# Electronical_dice.net
KiCad netlist of a schematic drawn in EAGLE
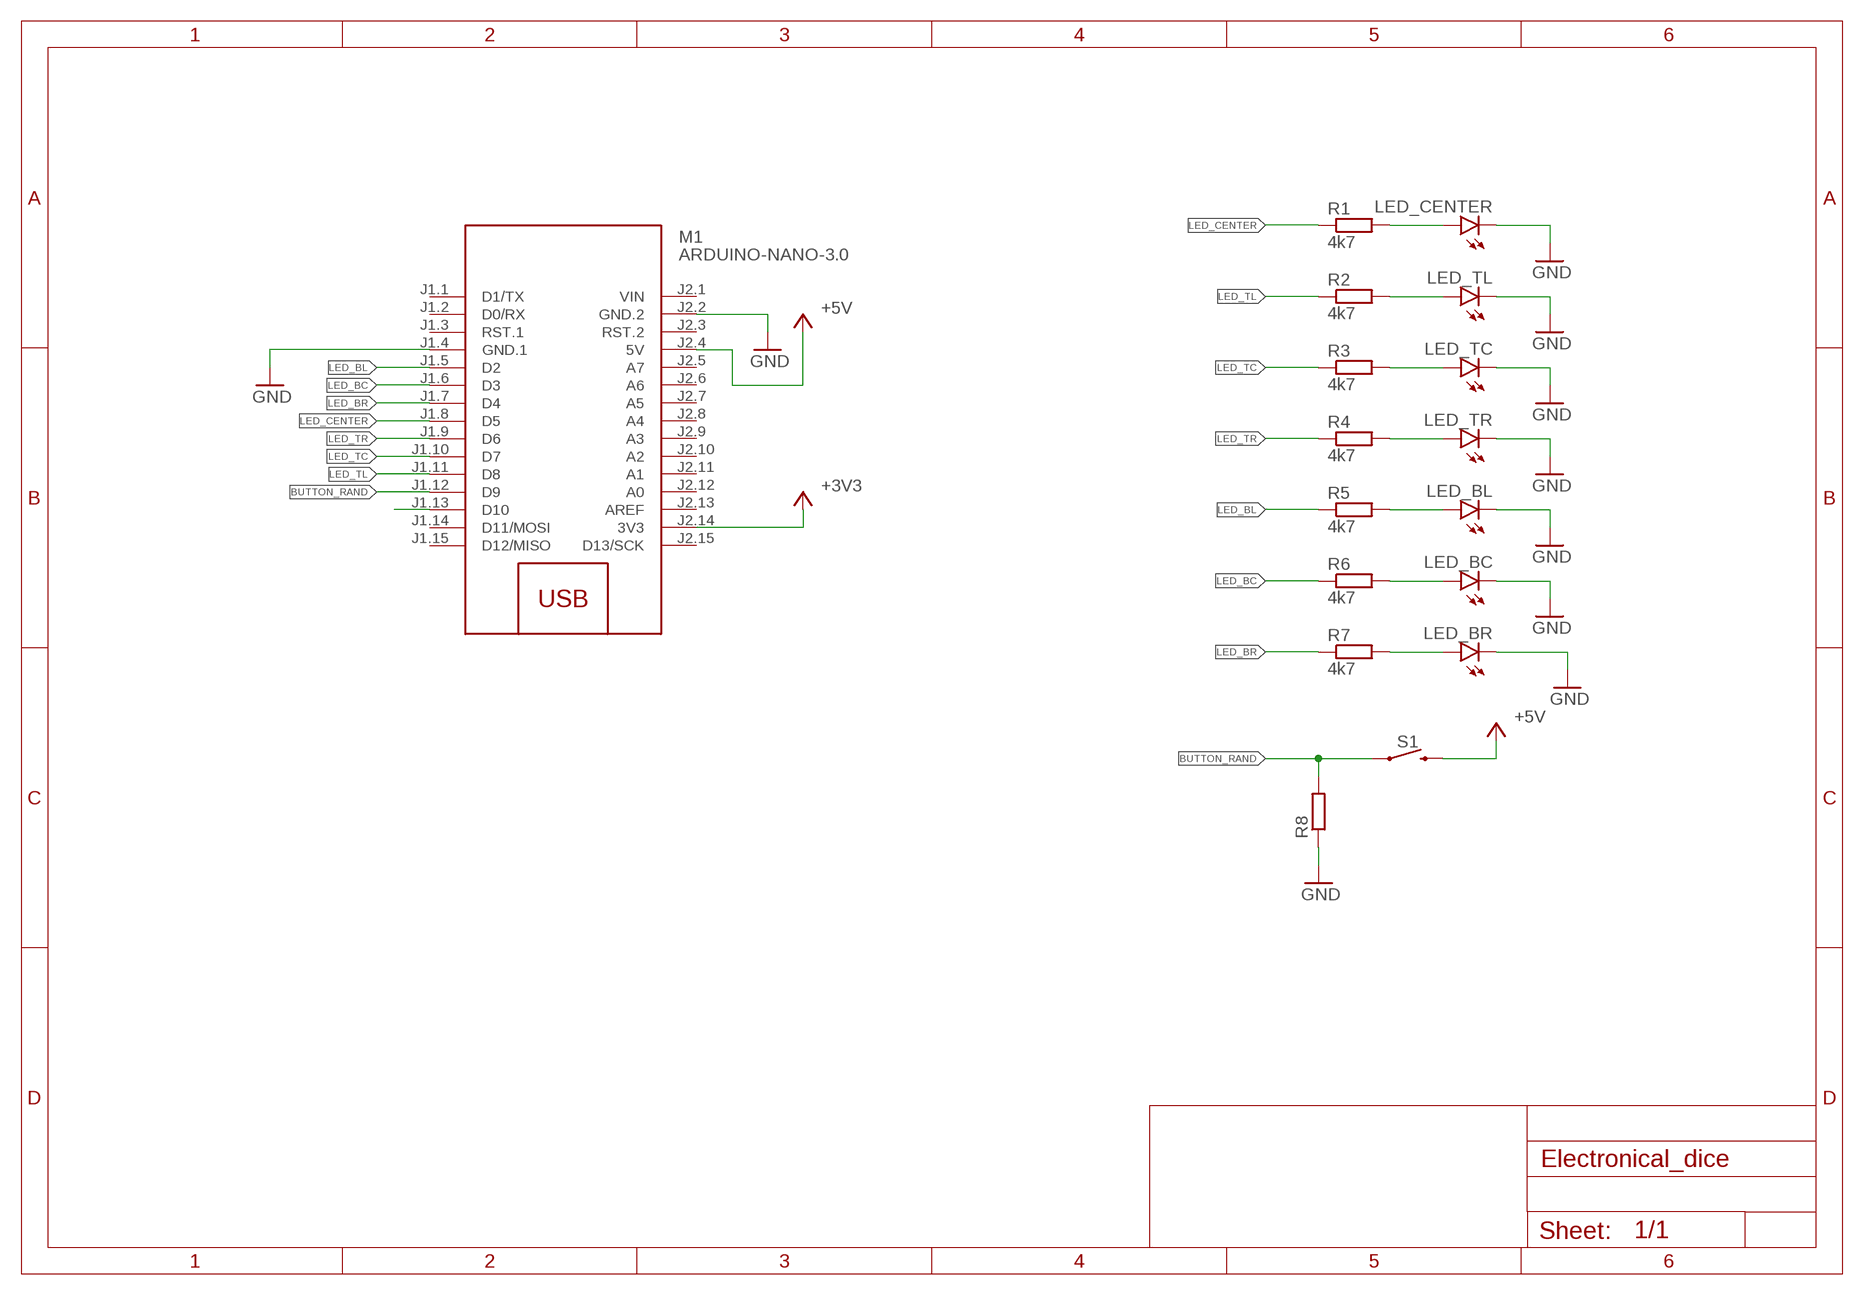
[diagram p0: schematic, sheet 1]

(export (version "E")
  (design (tool "Eeschema 10.0.6"))
  (components
    (comp (ref "LED_BC")
      (value "LED_RADIAL_RED")
      (footprint "eagle-import:LEDRD254W60D565H860B")
      (libsource (lib "eagle-import") (part "LED_RADIALRED_"))
    )
    (comp (ref "LED_BL")
      (value "LED_RADIAL_RED")
      (footprint "eagle-import:LEDRD254W60D565H860B")
      (libsource (lib "eagle-import") (part "LED_RADIALRED_"))
    )
    (comp (ref "LED_BR")
      (value "LED_RADIAL_RED")
      (footprint "eagle-import:LEDRD254W60D565H860B")
      (libsource (lib "eagle-import") (part "LED_RADIALRED_"))
    )
    (comp (ref "LED_CENTER")
      (value "LED_RADIAL_RED")
      (footprint "eagle-import:LEDRD254W60D565H860B")
      (libsource (lib "eagle-import") (part "LED_RADIALRED_"))
    )
    (comp (ref "LED_TC")
      (value "LED_RADIAL_RED")
      (footprint "eagle-import:LEDRD254W60D565H860B")
      (libsource (lib "eagle-import") (part "LED_RADIALRED_"))
    )
    (comp (ref "LED_TL")
      (value "LED_RADIAL_RED")
      (footprint "eagle-import:LEDRD254W60D565H860B")
      (libsource (lib "eagle-import") (part "LED_RADIALRED_"))
    )
    (comp (ref "LED_TR")
      (value "LED_RADIAL_RED")
      (footprint "eagle-import:LEDRD254W60D565H860B")
      (libsource (lib "eagle-import") (part "LED_RADIALRED_"))
    )
    (comp (ref "M1")
      (value "ARDUINO-NANO-3.0")
      (footprint "eagle-import:ARDUINO-NANO-3.0")
      (libsource (lib "eagle-import") (part "ARDUINO-NANO-3.0"))
    )
    (comp (ref "R1")
      (value "4k7")
      (footprint "eagle-import:0207_7")
      (libsource (lib "eagle-import") (part "R-EU_0207/7"))
    )
    (comp (ref "R2")
      (value "4k7")
      (footprint "eagle-import:0207_7")
      (libsource (lib "eagle-import") (part "R-EU_0207/7"))
    )
    (comp (ref "R3")
      (value "4k7")
      (footprint "eagle-import:0207_7")
      (libsource (lib "eagle-import") (part "R-EU_0207/7"))
    )
    (comp (ref "R4")
      (value "4k7")
      (footprint "eagle-import:0207_7")
      (libsource (lib "eagle-import") (part "R-EU_0207/7"))
    )
    (comp (ref "R5")
      (value "4k7")
      (footprint "eagle-import:0207_7")
      (libsource (lib "eagle-import") (part "R-EU_0207/7"))
    )
    (comp (ref "R6")
      (value "4k7")
      (footprint "eagle-import:0207_7")
      (libsource (lib "eagle-import") (part "R-EU_0207/7"))
    )
    (comp (ref "R7")
      (value "4k7")
      (footprint "eagle-import:0207_7")
      (libsource (lib "eagle-import") (part "R-EU_0207/7"))
    )
    (comp (ref "R8")
      (value "R-EU_0207/7")
      (footprint "eagle-import:0207_7")
      (libsource (lib "eagle-import") (part "R-EU_0207/7"))
    )
    (comp (ref "S1")
      (value "MOMENTARY-SWITCH-SPST-PTH-6.0MM")
      (footprint "eagle-import:TACTILE_SWITCH_PTH_6.0MM")
      (libsource (lib "eagle-import") (part "MOMENTARY-SWITCH-SPST-PTH-6.0MM"))
    )
  )
  (nets
    (net (code "1") (name "+3V3") (class "Default")
      (node (ref "M1") (pin "J2.14") (pinfunction "3V3_J2.14") (pintype "power_in"))
    )
    (net (code "2") (name "+5V") (class "Default")
      (node (ref "M1") (pin "J2.4") (pinfunction "5V_J2.4") (pintype "power_in"))
      (node (ref "S1") (pin "3") (pinfunction "2_3") (pintype "passive"))
    )
    (net (code "3") (name "/VIN") (class "Default")
      (node (ref "M1") (pin "J2.1") (pinfunction "VIN_J2.1") (pintype "power_in"))
    )
    (net (code "4") (name "BUTTON_RAND") (class "Default")
      (node (ref "M1") (pin "J1.12") (pinfunction "D9_J1.12") (pintype "bidirectional"))
      (node (ref "R8") (pin "2") (pinfunction "2_2") (pintype "passive"))
      (node (ref "S1") (pin "1") (pinfunction "1_1") (pintype "passive"))
    )
    (net (code "5") (name "GND") (class "Default")
      (node (ref "LED_BC") (pin "2") (pinfunction "C_2") (pintype "passive"))
      (node (ref "LED_BL") (pin "2") (pinfunction "C_2") (pintype "passive"))
      (node (ref "LED_BR") (pin "2") (pinfunction "C_2") (pintype "passive"))
      (node (ref "LED_CENTER") (pin "2") (pinfunction "C_2") (pintype "passive"))
      (node (ref "LED_TC") (pin "2") (pinfunction "C_2") (pintype "passive"))
      (node (ref "LED_TL") (pin "2") (pinfunction "C_2") (pintype "passive"))
      (node (ref "LED_TR") (pin "2") (pinfunction "C_2") (pintype "passive"))
      (node (ref "M1") (pin "J1.4") (pinfunction "GND.1_J1.4") (pintype "power_in"))
      (node (ref "M1") (pin "J2.2") (pinfunction "GND.2_J2.2") (pintype "power_in"))
      (node (ref "R8") (pin "1") (pinfunction "1_1") (pintype "passive"))
    )
    (net (code "6") (name "LED_BC") (class "Default")
      (node (ref "M1") (pin "J1.6") (pinfunction "D3_J1.6") (pintype "bidirectional"))
      (node (ref "R6") (pin "1") (pinfunction "1_1") (pintype "passive"))
    )
    (net (code "7") (name "LED_BL") (class "Default")
      (node (ref "M1") (pin "J1.5") (pinfunction "D2_J1.5") (pintype "bidirectional"))
      (node (ref "R5") (pin "1") (pinfunction "1_1") (pintype "passive"))
    )
    (net (code "8") (name "LED_BR") (class "Default")
      (node (ref "M1") (pin "J1.7") (pinfunction "D4_J1.7") (pintype "bidirectional"))
      (node (ref "R7") (pin "1") (pinfunction "1_1") (pintype "passive"))
    )
    (net (code "9") (name "LED_CENTER") (class "Default")
      (node (ref "M1") (pin "J1.8") (pinfunction "D5_J1.8") (pintype "bidirectional"))
      (node (ref "R1") (pin "1") (pinfunction "1_1") (pintype "passive"))
    )
    (net (code "10") (name "LED_TC") (class "Default")
      (node (ref "M1") (pin "J1.10") (pinfunction "D7_J1.10") (pintype "bidirectional"))
      (node (ref "R3") (pin "1") (pinfunction "1_1") (pintype "passive"))
    )
    (net (code "11") (name "LED_TL") (class "Default")
      (node (ref "M1") (pin "J1.11") (pinfunction "D8_J1.11") (pintype "bidirectional"))
      (node (ref "R2") (pin "1") (pinfunction "1_1") (pintype "passive"))
    )
    (net (code "12") (name "LED_TR") (class "Default")
      (node (ref "M1") (pin "J1.9") (pinfunction "D6_J1.9") (pintype "bidirectional"))
      (node (ref "R4") (pin "1") (pinfunction "1_1") (pintype "passive"))
    )
    (net (code "13") (name "Net-(LED_BC-A)") (class "Default")
      (node (ref "LED_BC") (pin "1") (pinfunction "A_1") (pintype "passive"))
      (node (ref "R6") (pin "2") (pinfunction "2_2") (pintype "passive"))
    )
    (net (code "14") (name "Net-(LED_BL-A)") (class "Default")
      (node (ref "LED_BL") (pin "1") (pinfunction "A_1") (pintype "passive"))
      (node (ref "R5") (pin "2") (pinfunction "2_2") (pintype "passive"))
    )
    (net (code "15") (name "Net-(LED_BR-A)") (class "Default")
      (node (ref "LED_BR") (pin "1") (pinfunction "A_1") (pintype "passive"))
      (node (ref "R7") (pin "2") (pinfunction "2_2") (pintype "passive"))
    )
    (net (code "16") (name "Net-(LED_CENTER-A)") (class "Default")
      (node (ref "LED_CENTER") (pin "1") (pinfunction "A_1") (pintype "passive"))
      (node (ref "R1") (pin "2") (pinfunction "2_2") (pintype "passive"))
    )
    (net (code "17") (name "Net-(LED_TC-A)") (class "Default")
      (node (ref "LED_TC") (pin "1") (pinfunction "A_1") (pintype "passive"))
      (node (ref "R3") (pin "2") (pinfunction "2_2") (pintype "passive"))
    )
    (net (code "18") (name "Net-(LED_TL-A)") (class "Default")
      (node (ref "LED_TL") (pin "1") (pinfunction "A_1") (pintype "passive"))
      (node (ref "R2") (pin "2") (pinfunction "2_2") (pintype "passive"))
    )
    (net (code "19") (name "Net-(LED_TR-A)") (class "Default")
      (node (ref "LED_TR") (pin "1") (pinfunction "A_1") (pintype "passive"))
      (node (ref "R4") (pin "2") (pinfunction "2_2") (pintype "passive"))
    )
    (net (code "20") (name "unconnected-(M1-A0-PadJ2.12)") (class "Default")
      (node (ref "M1") (pin "J2.12") (pinfunction "A0_J2.12") (pintype "bidirectional"))
    )
    (net (code "21") (name "unconnected-(M1-A1-PadJ2.11)") (class "Default")
      (node (ref "M1") (pin "J2.11") (pinfunction "A1_J2.11") (pintype "bidirectional"))
    )
    (net (code "22") (name "unconnected-(M1-A2-PadJ2.10)") (class "Default")
      (node (ref "M1") (pin "J2.10") (pinfunction "A2_J2.10") (pintype "bidirectional"))
    )
    (net (code "23") (name "unconnected-(M1-A3-PadJ2.9)") (class "Default")
      (node (ref "M1") (pin "J2.9") (pinfunction "A3_J2.9") (pintype "bidirectional"))
    )
    (net (code "24") (name "unconnected-(M1-A4-PadJ2.8)") (class "Default")
      (node (ref "M1") (pin "J2.8") (pinfunction "A4_J2.8") (pintype "bidirectional"))
    )
    (net (code "25") (name "unconnected-(M1-A5-PadJ2.7)") (class "Default")
      (node (ref "M1") (pin "J2.7") (pinfunction "A5_J2.7") (pintype "bidirectional"))
    )
    (net (code "26") (name "unconnected-(M1-A6-PadJ2.6)") (class "Default")
      (node (ref "M1") (pin "J2.6") (pinfunction "A6_J2.6") (pintype "bidirectional"))
    )
    (net (code "27") (name "unconnected-(M1-A7-PadJ2.5)") (class "Default")
      (node (ref "M1") (pin "J2.5") (pinfunction "A7_J2.5") (pintype "bidirectional"))
    )
    (net (code "28") (name "unconnected-(M1-AREF-PadJ2.13)") (class "Default")
      (node (ref "M1") (pin "J2.13") (pinfunction "AREF_J2.13") (pintype "bidirectional"))
    )
    (net (code "29") (name "unconnected-(M1-D0{slash}RX-PadJ1.2)") (class "Default")
      (node (ref "M1") (pin "J1.2") (pinfunction "D0/RX_J1.2") (pintype "bidirectional"))
    )
    (net (code "30") (name "unconnected-(M1-D1{slash}TX-PadJ1.1)") (class "Default")
      (node (ref "M1") (pin "J1.1") (pinfunction "D1/TX_J1.1") (pintype "bidirectional"))
    )
    (net (code "31") (name "unconnected-(M1-D10-PadJ1.13)") (class "Default")
      (node (ref "M1") (pin "J1.13") (pinfunction "D10_J1.13") (pintype "bidirectional"))
    )
    (net (code "32") (name "unconnected-(M1-D11{slash}MOSI-PadJ1.14)") (class "Default")
      (node (ref "M1") (pin "J1.14") (pinfunction "D11/MOSI_J1.14") (pintype "bidirectional"))
    )
    (net (code "33") (name "unconnected-(M1-D12{slash}MISO-PadJ1.15)") (class "Default")
      (node (ref "M1") (pin "J1.15") (pinfunction "D12/MISO_J1.15") (pintype "bidirectional"))
    )
    (net (code "34") (name "unconnected-(M1-D13{slash}SCK-PadJ2.15)") (class "Default")
      (node (ref "M1") (pin "J2.15") (pinfunction "D13/SCK_J2.15") (pintype "bidirectional"))
    )
    (net (code "35") (name "unconnected-(M1-RST.1-PadJ1.3)") (class "Default")
      (node (ref "M1") (pin "J1.3") (pinfunction "RST.1_J1.3") (pintype "bidirectional"))
    )
    (net (code "36") (name "unconnected-(M1-RST.2-PadJ2.3)") (class "Default")
      (node (ref "M1") (pin "J2.3") (pinfunction "RST.2_J2.3") (pintype "bidirectional"))
    )
  )
)
